# spdif_B.net
KiCad netlist of a schematic drawn in EAGLE
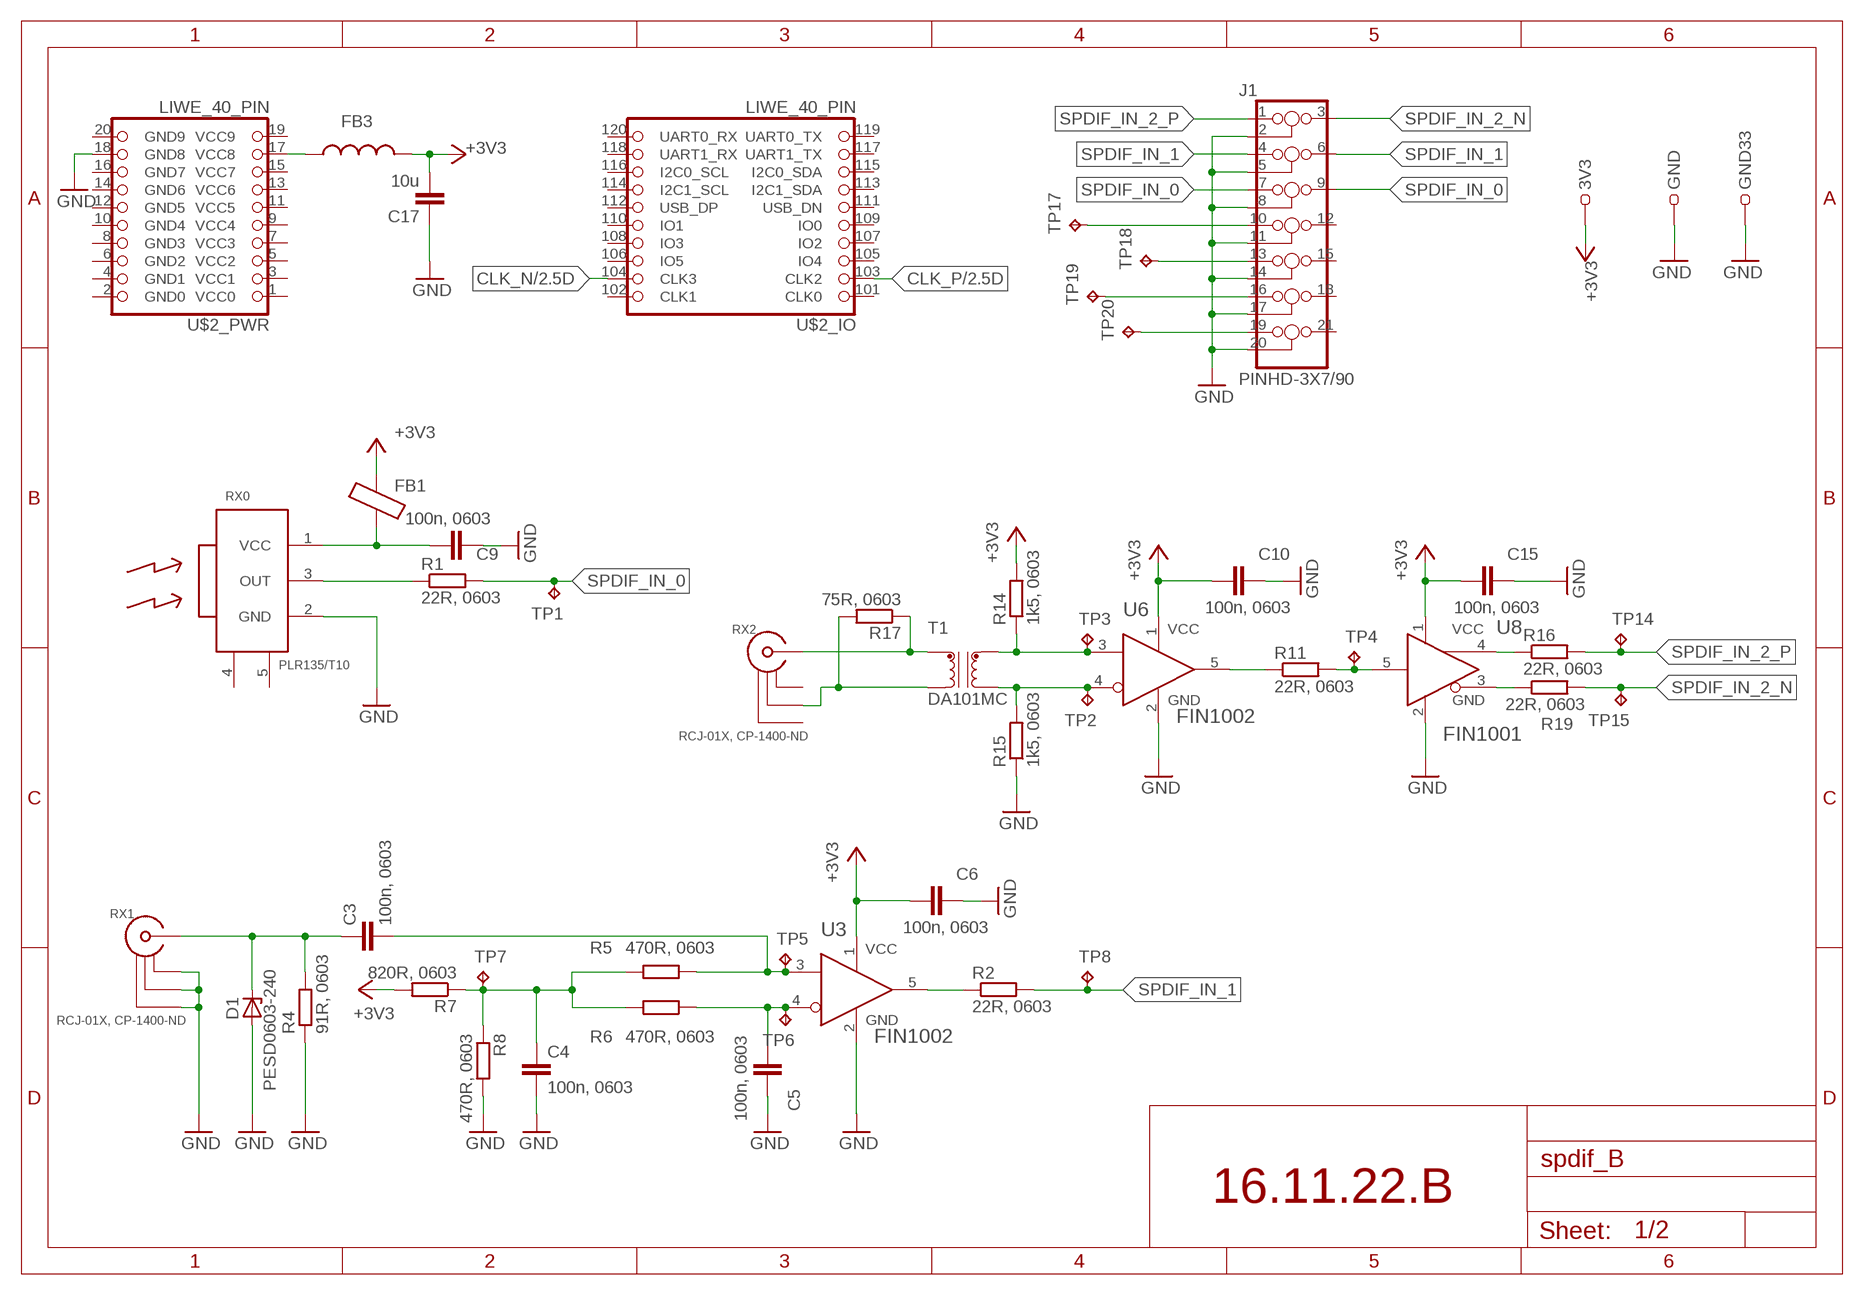
[diagram p0: schematic, sheet 1]
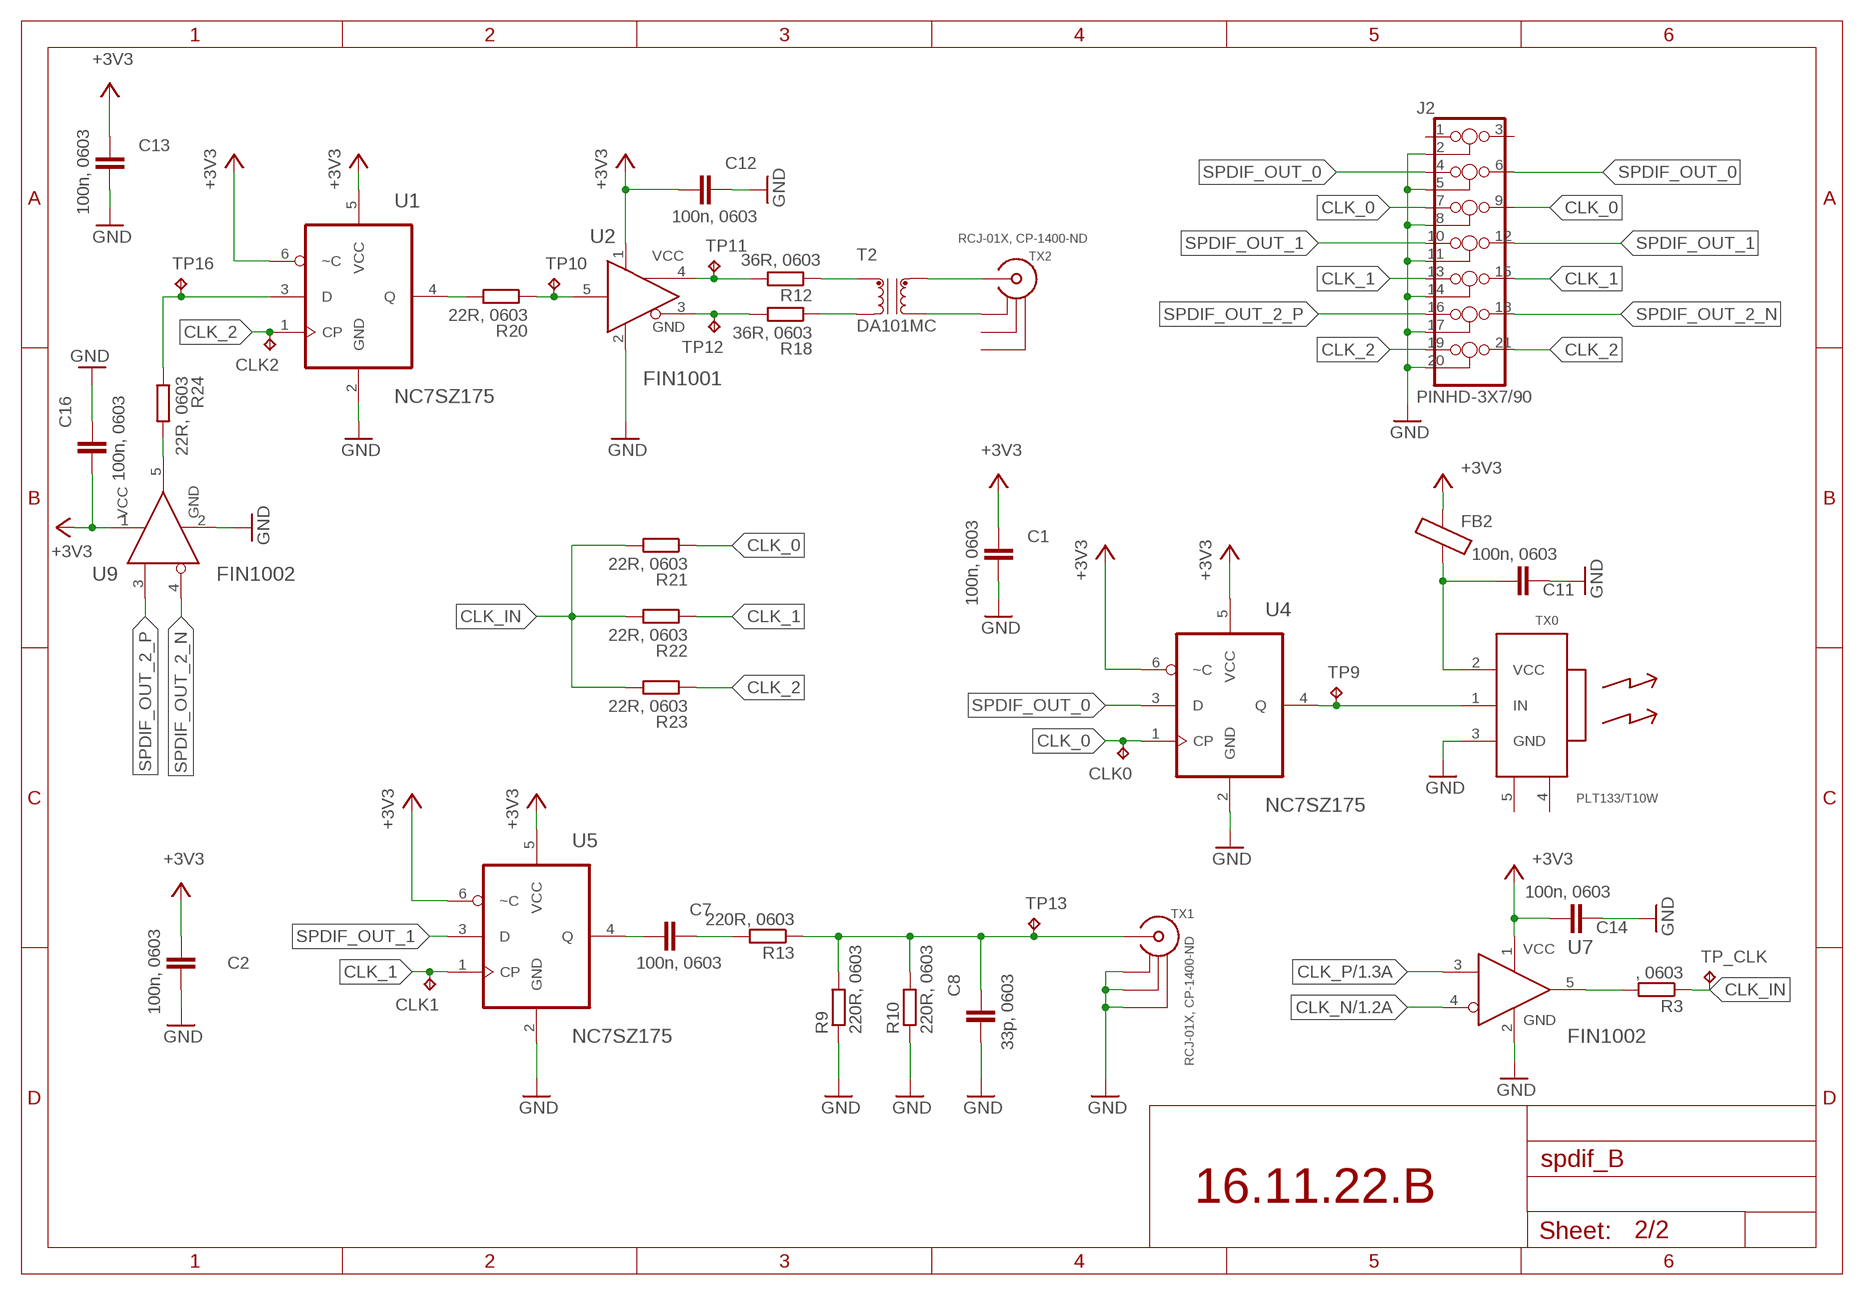
[diagram p1: schematic, sheet 2]

(export (version "E")
  (design (tool "Eeschema 10.0.6"))
  (components
    (comp (ref "3V3")
      (value "TEST-22-MULTICOMP")
      (footprint "eagle-import:TEST_1MM")
      (libsource (lib "eagle-import") (part "TEST-22-MULTICOMP"))
    )
    (comp (ref "C3")
      (value "100n, 0603")
      (footprint "eagle-import:C0603")
      (libsource (lib "eagle-import") (part "C-EUC0603"))
    )
    (comp (ref "C4")
      (value "100n, 0603")
      (footprint "eagle-import:C0603")
      (libsource (lib "eagle-import") (part "C-EUC0603"))
    )
    (comp (ref "C5")
      (value "100n, 0603")
      (footprint "eagle-import:C0603")
      (libsource (lib "eagle-import") (part "C-EUC0603"))
    )
    (comp (ref "C6")
      (value "100n, 0603")
      (footprint "eagle-import:C0603")
      (libsource (lib "eagle-import") (part "C-EUC0603"))
    )
    (comp (ref "C9")
      (value "100n, 0603")
      (footprint "eagle-import:C0603")
      (libsource (lib "eagle-import") (part "C-EUC0603"))
    )
    (comp (ref "C10")
      (value "100n, 0603")
      (footprint "eagle-import:C0603")
      (libsource (lib "eagle-import") (part "C-EUC0603"))
    )
    (comp (ref "C15")
      (value "100n, 0603")
      (footprint "eagle-import:C0603")
      (libsource (lib "eagle-import") (part "C-EUC0603"))
    )
    (comp (ref "C17")
      (value "10u")
      (footprint "eagle-import:C0805")
      (libsource (lib "eagle-import") (part "C-EUC0805"))
    )
    (comp (ref "D1")
      (value "PESD0603-240")
      (footprint "eagle-import:L0603")
      (libsource (lib "eagle-import") (part "ZDPESD0603-240"))
    )
    (comp (ref "FB1")
      (value "FB_0603")
      (footprint "eagle-import:L0603")
      (libsource (lib "eagle-import") (part "FB_0603"))
    )
    (comp (ref "FB3")
      (value "L0603(1608)")
      (footprint "eagle-import:L0603")
      (libsource (lib "eagle-import") (part "L0603(1608)"))
    )
    (comp (ref "GND")
      (value "TEST-22-MULTICOMP")
      (footprint "eagle-import:TEST_1MM")
      (libsource (lib "eagle-import") (part "TEST-22-MULTICOMP"))
    )
    (comp (ref "GND33")
      (value "TEST-22-MULTICOMP")
      (footprint "eagle-import:TEST_1MM")
      (libsource (lib "eagle-import") (part "TEST-22-MULTICOMP"))
    )
    (comp (ref "J1")
      (value "PINHD-3X7/90")
      (footprint "eagle-import:3X07_90")
      (libsource (lib "eagle-import") (part "PINHD-3X7/90"))
    )
    (comp (ref "R1")
      (value "22R, 0603")
      (footprint "eagle-import:R0603")
      (libsource (lib "eagle-import") (part "R-EU_R0603"))
    )
    (comp (ref "R2")
      (value "22R, 0603")
      (footprint "eagle-import:R0603")
      (libsource (lib "eagle-import") (part "R-EU_R0603"))
    )
    (comp (ref "R4")
      (value "91R, 0603")
      (footprint "eagle-import:R0603")
      (libsource (lib "eagle-import") (part "R-EU_R0603"))
    )
    (comp (ref "R5")
      (value "470R, 0603")
      (footprint "eagle-import:R0603")
      (libsource (lib "eagle-import") (part "R-EU_R0603"))
    )
    (comp (ref "R6")
      (value "470R, 0603")
      (footprint "eagle-import:R0603")
      (libsource (lib "eagle-import") (part "R-EU_R0603"))
    )
    (comp (ref "R7")
      (value "820R, 0603")
      (footprint "eagle-import:R0603")
      (libsource (lib "eagle-import") (part "R-EU_R0603"))
    )
    (comp (ref "R8")
      (value "470R, 0603")
      (footprint "eagle-import:R0603")
      (libsource (lib "eagle-import") (part "R-EU_R0603"))
    )
    (comp (ref "R11")
      (value "22R, 0603")
      (footprint "eagle-import:R0603")
      (libsource (lib "eagle-import") (part "R-EU_R0603"))
    )
    (comp (ref "R14")
      (value "1k5, 0603")
      (footprint "eagle-import:R0603")
      (libsource (lib "eagle-import") (part "R-EU_R0603"))
    )
    (comp (ref "R15")
      (value "1k5, 0603")
      (footprint "eagle-import:R0603")
      (libsource (lib "eagle-import") (part "R-EU_R0603"))
    )
    (comp (ref "R16")
      (value "22R, 0603")
      (footprint "eagle-import:R0603")
      (libsource (lib "eagle-import") (part "R-EU_R0603"))
    )
    (comp (ref "R17")
      (value "75R, 0603")
      (footprint "eagle-import:R0603")
      (libsource (lib "eagle-import") (part "R-EU_R0603"))
    )
    (comp (ref "R19")
      (value "22R, 0603")
      (footprint "eagle-import:R0603")
      (libsource (lib "eagle-import") (part "R-EU_R0603"))
    )
    (comp (ref "RX0")
      (value "PLR135/T10")
      (footprint "eagle-import:PLR135_T10")
      (libsource (lib "eagle-import") (part "PLR135_T10"))
    )
    (comp (ref "RX1")
      (value "RCJ-01X, CP-1400-ND")
      (footprint "eagle-import:RCJ-01X")
      (libsource (lib "eagle-import") (part "RCJ-01X"))
    )
    (comp (ref "RX2")
      (value "RCJ-01X, CP-1400-ND")
      (footprint "eagle-import:RCJ-01X")
      (libsource (lib "eagle-import") (part "RCJ-01X"))
    )
    (comp (ref "T1")
      (value "DA101MC")
      (footprint "eagle-import:DA101MC")
      (libsource (lib "eagle-import") (part "DA101MC"))
    )
    (comp (ref "TP1")
      (value "TPB1,27")
      (footprint "eagle-import:B1,27")
      (libsource (lib "eagle-import") (part "TPB1,27"))
    )
    (comp (ref "TP2")
      (value "TPB1,27")
      (footprint "eagle-import:B1,27")
      (libsource (lib "eagle-import") (part "TPB1,27"))
    )
    (comp (ref "TP3")
      (value "TPB1,27")
      (footprint "eagle-import:B1,27")
      (libsource (lib "eagle-import") (part "TPB1,27"))
    )
    (comp (ref "TP4")
      (value "TPB1,27")
      (footprint "eagle-import:B1,27")
      (libsource (lib "eagle-import") (part "TPB1,27"))
    )
    (comp (ref "TP5")
      (value "TPB1,27")
      (footprint "eagle-import:B1,27")
      (libsource (lib "eagle-import") (part "TPB1,27"))
    )
    (comp (ref "TP6")
      (value "TPB1,27")
      (footprint "eagle-import:B1,27")
      (libsource (lib "eagle-import") (part "TPB1,27"))
    )
    (comp (ref "TP7")
      (value "TPB1,27")
      (footprint "eagle-import:B1,27")
      (libsource (lib "eagle-import") (part "TPB1,27"))
    )
    (comp (ref "TP8")
      (value "TPB1,27")
      (footprint "eagle-import:B1,27")
      (libsource (lib "eagle-import") (part "TPB1,27"))
    )
    (comp (ref "TP14")
      (value "TPB1,27")
      (footprint "eagle-import:B1,27")
      (libsource (lib "eagle-import") (part "TPB1,27"))
    )
    (comp (ref "TP15")
      (value "TPB1,27")
      (footprint "eagle-import:B1,27")
      (libsource (lib "eagle-import") (part "TPB1,27"))
    )
    (comp (ref "TP17")
      (value "TPB1,27")
      (footprint "eagle-import:B1,27")
      (libsource (lib "eagle-import") (part "TPB1,27"))
    )
    (comp (ref "TP18")
      (value "TPB1,27")
      (footprint "eagle-import:B1,27")
      (libsource (lib "eagle-import") (part "TPB1,27"))
    )
    (comp (ref "TP19")
      (value "TPB1,27")
      (footprint "eagle-import:B1,27")
      (libsource (lib "eagle-import") (part "TPB1,27"))
    )
    (comp (ref "TP20")
      (value "TPB1,27")
      (footprint "eagle-import:B1,27")
      (libsource (lib "eagle-import") (part "TPB1,27"))
    )
    (comp (ref "U$2")
      (value "LIWE_40_PIN")
      (footprint "eagle-import:LIWE_40_PIN_8X8")
      (libsource (lib "eagle-import") (part "LIWE_40_PIN"))
    )
    (comp (ref "U3")
      (value "FIN1002")
      (footprint "eagle-import:SOT95P280X140-5N")
      (libsource (lib "eagle-import") (part "FIN1002"))
    )
    (comp (ref "U6")
      (value "FIN1002")
      (footprint "eagle-import:SOT95P280X140-5N")
      (libsource (lib "eagle-import") (part "FIN1002"))
    )
    (comp (ref "U8")
      (value "FIN1001")
      (footprint "eagle-import:SOT95P280X140-5N")
      (libsource (lib "eagle-import") (part "FIN1001"))
    )
    (comp (ref "C1")
      (value "100n, 0603")
      (footprint "eagle-import:C0603")
      (libsource (lib "eagle-import") (part "C-EUC0603"))
    )
    (comp (ref "C2")
      (value "100n, 0603")
      (footprint "eagle-import:C0603")
      (libsource (lib "eagle-import") (part "C-EUC0603"))
    )
    (comp (ref "C7")
      (value "100n, 0603")
      (footprint "eagle-import:C0603")
      (libsource (lib "eagle-import") (part "C-EUC0603"))
    )
    (comp (ref "C8")
      (value "33p, 0603")
      (footprint "eagle-import:C0603")
      (libsource (lib "eagle-import") (part "C-EUC0603"))
    )
    (comp (ref "C11")
      (value "100n, 0603")
      (footprint "eagle-import:C0603")
      (libsource (lib "eagle-import") (part "C-EUC0603"))
    )
    (comp (ref "C12")
      (value "100n, 0603")
      (footprint "eagle-import:C0603")
      (libsource (lib "eagle-import") (part "C-EUC0603"))
    )
    (comp (ref "C13")
      (value "100n, 0603")
      (footprint "eagle-import:C0603")
      (libsource (lib "eagle-import") (part "C-EUC0603"))
    )
    (comp (ref "C14")
      (value "100n, 0603")
      (footprint "eagle-import:C0603")
      (libsource (lib "eagle-import") (part "C-EUC0603"))
    )
    (comp (ref "C16")
      (value "100n, 0603")
      (footprint "eagle-import:C0603")
      (libsource (lib "eagle-import") (part "C-EUC0603"))
    )
    (comp (ref "CLK0")
      (value "TPB1,27")
      (footprint "eagle-import:B1,27")
      (libsource (lib "eagle-import") (part "TPB1,27"))
    )
    (comp (ref "CLK1")
      (value "TPB1,27")
      (footprint "eagle-import:B1,27")
      (libsource (lib "eagle-import") (part "TPB1,27"))
    )
    (comp (ref "CLK2")
      (value "TPB1,27")
      (footprint "eagle-import:B1,27")
      (libsource (lib "eagle-import") (part "TPB1,27"))
    )
    (comp (ref "FB2")
      (value "FB_0603")
      (footprint "eagle-import:L0603")
      (libsource (lib "eagle-import") (part "FB_0603"))
    )
    (comp (ref "J2")
      (value "PINHD-3X7/90")
      (footprint "eagle-import:3X07_90")
      (libsource (lib "eagle-import") (part "PINHD-3X7/90"))
    )
    (comp (ref "R3")
      (value ", 0603")
      (footprint "eagle-import:R0603")
      (libsource (lib "eagle-import") (part "R-EU_R0603"))
    )
    (comp (ref "R9")
      (value "220R, 0603")
      (footprint "eagle-import:R0603")
      (libsource (lib "eagle-import") (part "R-EU_R0603"))
    )
    (comp (ref "R10")
      (value "220R, 0603")
      (footprint "eagle-import:R0603")
      (libsource (lib "eagle-import") (part "R-EU_R0603"))
    )
    (comp (ref "R12")
      (value "36R, 0603")
      (footprint "eagle-import:R0603")
      (libsource (lib "eagle-import") (part "R-EU_R0603"))
    )
    (comp (ref "R13")
      (value "220R, 0603")
      (footprint "eagle-import:R0603")
      (libsource (lib "eagle-import") (part "R-EU_R0603"))
    )
    (comp (ref "R18")
      (value "36R, 0603")
      (footprint "eagle-import:R0603")
      (libsource (lib "eagle-import") (part "R-EU_R0603"))
    )
    (comp (ref "R20")
      (value "22R, 0603")
      (footprint "eagle-import:R0603")
      (libsource (lib "eagle-import") (part "R-EU_R0603"))
    )
    (comp (ref "R21")
      (value "22R, 0603")
      (footprint "eagle-import:R0603")
      (libsource (lib "eagle-import") (part "R-EU_R0603"))
    )
    (comp (ref "R22")
      (value "22R, 0603")
      (footprint "eagle-import:R0603")
      (libsource (lib "eagle-import") (part "R-EU_R0603"))
    )
    (comp (ref "R23")
      (value "22R, 0603")
      (footprint "eagle-import:R0603")
      (libsource (lib "eagle-import") (part "R-EU_R0603"))
    )
    (comp (ref "R24")
      (value "22R, 0603")
      (footprint "eagle-import:R0603")
      (libsource (lib "eagle-import") (part "R-EU_R0603"))
    )
    (comp (ref "T2")
      (value "DA101MC")
      (footprint "eagle-import:DA101MC")
      (libsource (lib "eagle-import") (part "DA101MC"))
    )
    (comp (ref "TP9")
      (value "TPB1,27")
      (footprint "eagle-import:B1,27")
      (libsource (lib "eagle-import") (part "TPB1,27"))
    )
    (comp (ref "TP10")
      (value "TPB1,27")
      (footprint "eagle-import:B1,27")
      (libsource (lib "eagle-import") (part "TPB1,27"))
    )
    (comp (ref "TP11")
      (value "TPB1,27")
      (footprint "eagle-import:B1,27")
      (libsource (lib "eagle-import") (part "TPB1,27"))
    )
    (comp (ref "TP12")
      (value "TPB1,27")
      (footprint "eagle-import:B1,27")
      (libsource (lib "eagle-import") (part "TPB1,27"))
    )
    (comp (ref "TP13")
      (value "TPB1,27")
      (footprint "eagle-import:B1,27")
      (libsource (lib "eagle-import") (part "TPB1,27"))
    )
    (comp (ref "TP16")
      (value "TPB1,27")
      (footprint "eagle-import:B1,27")
      (libsource (lib "eagle-import") (part "TPB1,27"))
    )
    (comp (ref "TP_CLK")
      (value "TPB1,27")
      (footprint "eagle-import:B1,27")
      (libsource (lib "eagle-import") (part "TPB1,27"))
    )
    (comp (ref "TX0")
      (value "PLT133/T10W")
      (footprint "eagle-import:PLT133_T10W")
      (libsource (lib "eagle-import") (part "PLT133_T10W"))
    )
    (comp (ref "TX1")
      (value "RCJ-01X, CP-1400-ND")
      (footprint "eagle-import:RCJ-01X")
      (libsource (lib "eagle-import") (part "RCJ-01X"))
    )
    (comp (ref "TX2")
      (value "RCJ-01X, CP-1400-ND")
      (footprint "eagle-import:RCJ-01X")
      (libsource (lib "eagle-import") (part "RCJ-01X"))
    )
    (comp (ref "U1")
      (value "NC7SZ175")
      (footprint "eagle-import:SOT65P210X110-6N")
      (libsource (lib "eagle-import") (part "NC7SZ175"))
    )
    (comp (ref "U2")
      (value "FIN1001")
      (footprint "eagle-import:SOT95P280X140-5N")
      (libsource (lib "eagle-import") (part "FIN1001"))
    )
    (comp (ref "U4")
      (value "NC7SZ175")
      (footprint "eagle-import:SOT65P210X110-6N")
      (libsource (lib "eagle-import") (part "NC7SZ175"))
    )
    (comp (ref "U5")
      (value "NC7SZ175")
      (footprint "eagle-import:SOT65P210X110-6N")
      (libsource (lib "eagle-import") (part "NC7SZ175"))
    )
    (comp (ref "U7")
      (value "FIN1002")
      (footprint "eagle-import:SOT95P280X140-5N")
      (libsource (lib "eagle-import") (part "FIN1002"))
    )
    (comp (ref "U9")
      (value "FIN1002")
      (footprint "eagle-import:SOT95P280X140-5N")
      (libsource (lib "eagle-import") (part "FIN1002"))
    )
  )
  (nets
    (net (code "1") (name "+3V3") (class "Default")
      (node (ref "3V3") (pin "1") (pinfunction "1_1") (pintype "passive"))
      (node (ref "C1") (pin "2") (pinfunction "2_2") (pintype "passive"))
      (node (ref "C10") (pin "2") (pinfunction "2_2") (pintype "passive"))
      (node (ref "C12") (pin "2") (pinfunction "2_2") (pintype "passive"))
      (node (ref "C13") (pin "2") (pinfunction "2_2") (pintype "passive"))
      (node (ref "C14") (pin "2") (pinfunction "2_2") (pintype "passive"))
      (node (ref "C15") (pin "2") (pinfunction "2_2") (pintype "passive"))
      (node (ref "C16") (pin "2") (pinfunction "2_2") (pintype "passive"))
      (node (ref "C17") (pin "2") (pinfunction "2_2") (pintype "passive"))
      (node (ref "C2") (pin "2") (pinfunction "2_2") (pintype "passive"))
      (node (ref "C6") (pin "2") (pinfunction "2_2") (pintype "passive"))
      (node (ref "FB1") (pin "2") (pinfunction "P$2_2") (pintype "bidirectional"))
      (node (ref "FB2") (pin "2") (pinfunction "P$2_2") (pintype "bidirectional"))
      (node (ref "FB3") (pin "2") (pinfunction "2_2") (pintype "passive"))
      (node (ref "R14") (pin "2") (pinfunction "2_2") (pintype "passive"))
      (node (ref "R7") (pin "2") (pinfunction "2_2") (pintype "passive"))
      (node (ref "U1") (pin "5") (pinfunction "VCC_5") (pintype "power_in"))
      (node (ref "U1") (pin "6") (pinfunction "~{C}_6") (pintype "input"))
      (node (ref "U2") (pin "1") (pinfunction "VCC_1") (pintype "power_in"))
      (node (ref "U3") (pin "1") (pinfunction "VCC_1") (pintype "power_in"))
      (node (ref "U4") (pin "5") (pinfunction "VCC_5") (pintype "power_in"))
      (node (ref "U4") (pin "6") (pinfunction "~{C}_6") (pintype "input"))
      (node (ref "U5") (pin "5") (pinfunction "VCC_5") (pintype "power_in"))
      (node (ref "U5") (pin "6") (pinfunction "~{C}_6") (pintype "input"))
      (node (ref "U6") (pin "1") (pinfunction "VCC_1") (pintype "power_in"))
      (node (ref "U7") (pin "1") (pinfunction "VCC_1") (pintype "power_in"))
      (node (ref "U8") (pin "1") (pinfunction "VCC_1") (pintype "power_in"))
      (node (ref "U9") (pin "1") (pinfunction "VCC_1") (pintype "power_in"))
    )
    (net (code "2") (name "CLK_0") (class "Default")
      (node (ref "CLK0") (pin "TP") (pinfunction "TP_TP") (pintype "input"))
      (node (ref "J2") (pin "7") (pinfunction "7_7") (pintype "passive"))
      (node (ref "J2") (pin "9") (pinfunction "9_9") (pintype "passive"))
      (node (ref "R21") (pin "1") (pinfunction "1_1") (pintype "passive"))
      (node (ref "U4") (pin "1") (pinfunction "CP_1") (pintype "input"))
    )
    (net (code "3") (name "CLK_1") (class "Default")
      (node (ref "CLK1") (pin "TP") (pinfunction "TP_TP") (pintype "input"))
      (node (ref "J2") (pin "13") (pinfunction "13_13") (pintype "passive"))
      (node (ref "J2") (pin "15") (pinfunction "15_15") (pintype "passive"))
      (node (ref "R22") (pin "1") (pinfunction "1_1") (pintype "passive"))
      (node (ref "U5") (pin "1") (pinfunction "CP_1") (pintype "input"))
    )
    (net (code "4") (name "CLK_2") (class "Default")
      (node (ref "CLK2") (pin "TP") (pinfunction "TP_TP") (pintype "input"))
      (node (ref "J2") (pin "19") (pinfunction "19_19") (pintype "passive"))
      (node (ref "J2") (pin "21") (pinfunction "21_21") (pintype "passive"))
      (node (ref "R23") (pin "1") (pinfunction "1_1") (pintype "passive"))
      (node (ref "U1") (pin "1") (pinfunction "CP_1") (pintype "input"))
    )
    (net (code "5") (name "CLK_IN") (class "Default")
      (node (ref "R21") (pin "2") (pinfunction "2_2") (pintype "passive"))
      (node (ref "R22") (pin "2") (pinfunction "2_2") (pintype "passive"))
      (node (ref "R23") (pin "2") (pinfunction "2_2") (pintype "passive"))
      (node (ref "R3") (pin "1") (pinfunction "1_1") (pintype "passive"))
      (node (ref "TP_CLK") (pin "TP") (pinfunction "TP_TP") (pintype "input"))
    )
    (net (code "6") (name "CLK_N") (class "Default")
      (node (ref "U$2") (pin "104") (pinfunction "CLK3_104") (pintype "passive"))
      (node (ref "U7") (pin "4") (pinfunction "RIN-_4") (pintype "input"))
    )
    (net (code "7") (name "CLK_P") (class "Default")
      (node (ref "U$2") (pin "103") (pinfunction "CLK2_103") (pintype "passive"))
      (node (ref "U7") (pin "3") (pinfunction "RIN+_3") (pintype "input"))
    )
    (net (code "8") (name "GND") (class "Default")
      (node (ref "C1") (pin "1") (pinfunction "1_1") (pintype "passive"))
      (node (ref "C10") (pin "1") (pinfunction "1_1") (pintype "passive"))
      (node (ref "C11") (pin "1") (pinfunction "1_1") (pintype "passive"))
      (node (ref "C12") (pin "1") (pinfunction "1_1") (pintype "passive"))
      (node (ref "C13") (pin "1") (pinfunction "1_1") (pintype "passive"))
      (node (ref "C14") (pin "1") (pinfunction "1_1") (pintype "passive"))
      (node (ref "C15") (pin "1") (pinfunction "1_1") (pintype "passive"))
      (node (ref "C16") (pin "1") (pinfunction "1_1") (pintype "passive"))
      (node (ref "C17") (pin "1") (pinfunction "1_1") (pintype "passive"))
      (node (ref "C2") (pin "1") (pinfunction "1_1") (pintype "passive"))
      (node (ref "C4") (pin "2") (pinfunction "2_2") (pintype "passive"))
      (node (ref "C5") (pin "1") (pinfunction "1_1") (pintype "passive"))
      (node (ref "C6") (pin "1") (pinfunction "1_1") (pintype "passive"))
      (node (ref "C8") (pin "2") (pinfunction "2_2") (pintype "passive"))
      (node (ref "C9") (pin "1") (pinfunction "1_1") (pintype "passive"))
      (node (ref "D1") (pin "1") (pinfunction "A_1") (pintype "passive"))
      (node (ref "GND") (pin "1") (pinfunction "1_1") (pintype "passive"))
      (node (ref "GND33") (pin "1") (pinfunction "1_1") (pintype "passive"))
      (node (ref "J1") (pin "11") (pinfunction "11_11") (pintype "passive"))
      (node (ref "J1") (pin "14") (pinfunction "14_14") (pintype "passive"))
      (node (ref "J1") (pin "17") (pinfunction "17_17") (pintype "passive"))
      (node (ref "J1") (pin "2") (pinfunction "2_2") (pintype "passive"))
      (node (ref "J1") (pin "20") (pinfunction "20_20") (pintype "passive"))
      (node (ref "J1") (pin "5") (pinfunction "5_5") (pintype "passive"))
      (node (ref "J1") (pin "8") (pinfunction "8_8") (pintype "passive"))
      (node (ref "J2") (pin "11") (pinfunction "11_11") (pintype "passive"))
      (node (ref "J2") (pin "14") (pinfunction "14_14") (pintype "passive"))
      (node (ref "J2") (pin "17") (pinfunction "17_17") (pintype "passive"))
      (node (ref "J2") (pin "2") (pinfunction "2_2") (pintype "passive"))
      (node (ref "J2") (pin "20") (pinfunction "20_20") (pintype "passive"))
      (node (ref "J2") (pin "5") (pinfunction "5_5") (pintype "passive"))
      (node (ref "J2") (pin "8") (pinfunction "8_8") (pintype "passive"))
      (node (ref "R10") (pin "1") (pinfunction "1_1") (pintype "passive"))
      (node (ref "R15") (pin "1") (pinfunction "1_1") (pintype "passive"))
      (node (ref "R4") (pin "1") (pinfunction "1_1") (pintype "passive"))
      (node (ref "R8") (pin "2") (pinfunction "2_2") (pintype "passive"))
      (node (ref "R9") (pin "1") (pinfunction "1_1") (pintype "passive"))
      (node (ref "RX0") (pin "2") (pinfunction "GND_2") (pintype "output"))
      (node (ref "RX1") (pin "20") (pinfunction "GND1_20") (pintype "output"))
      (node (ref "RX1") (pin "21") (pinfunction "GND2_21") (pintype "output"))
      (node (ref "RX1") (pin "22") (pinfunction "GND3_22") (pintype "output"))
      (node (ref "TX0") (pin "3") (pinfunction "GND_3") (pintype "output"))
      (node (ref "TX1") (pin "20") (pinfunction "GND1_20") (pintype "output"))
      (node (ref "TX1") (pin "21") (pinfunction "GND2_21") (pintype "output"))
      (node (ref "TX1") (pin "22") (pinfunction "GND3_22") (pintype "output"))
      (node (ref "U$2") (pin "18") (pinfunction "GND8_18") (pintype "passive"))
      (node (ref "U1") (pin "2") (pinfunction "GND_2") (pintype "passive"))
      (node (ref "U2") (pin "2") (pinfunction "GND_2") (pintype "passive"))
      (node (ref "U3") (pin "2") (pinfunction "GND_2") (pintype "passive"))
      (node (ref "U4") (pin "2") (pinfunction "GND_2") (pintype "passive"))
      (node (ref "U5") (pin "2") (pinfunction "GND_2") (pintype "passive"))
      (node (ref "U6") (pin "2") (pinfunction "GND_2") (pintype "passive"))
      (node (ref "U7") (pin "2") (pinfunction "GND_2") (pintype "passive"))
      (node (ref "U8") (pin "2") (pinfunction "GND_2") (pintype "passive"))
      (node (ref "U9") (pin "2") (pinfunction "GND_2") (pintype "passive"))
    )
    (net (code "9") (name "Net-(C4-Pad1)") (class "Default")
      (node (ref "C4") (pin "1") (pinfunction "1_1") (pintype "passive"))
      (node (ref "R5") (pin "2") (pinfunction "2_2") (pintype "passive"))
      (node (ref "R6") (pin "2") (pinfunction "2_2") (pintype "passive"))
      (node (ref "R7") (pin "1") (pinfunction "1_1") (pintype "passive"))
      (node (ref "R8") (pin "1") (pinfunction "1_1") (pintype "passive"))
      (node (ref "TP7") (pin "TP") (pinfunction "TP_TP") (pintype "input"))
    )
    (net (code "10") (name "Net-(C7-Pad1)") (class "Default")
      (node (ref "C7") (pin "1") (pinfunction "1_1") (pintype "passive"))
      (node (ref "R13") (pin "2") (pinfunction "2_2") (pintype "passive"))
    )
    (net (code "11") (name "Net-(D1-C)") (class "Default")
      (node (ref "C3") (pin "1") (pinfunction "1_1") (pintype "passive"))
      (node (ref "D1") (pin "2") (pinfunction "C_2") (pintype "passive"))
      (node (ref "R4") (pin "2") (pinfunction "2_2") (pintype "passive"))
      (node (ref "RX1") (pin "1") (pinfunction "SIG_1") (pintype "output"))
    )
    (net (code "12") (name "Net-(FB1-P$1)") (class "Default")
      (node (ref "C9") (pin "2") (pinfunction "2_2") (pintype "passive"))
      (node (ref "FB1") (pin "1") (pinfunction "P$1_1") (pintype "bidirectional"))
      (node (ref "RX0") (pin "1") (pinfunction "VCC_1") (pintype "output"))
    )
    (net (code "13") (name "Net-(FB2-P$1)") (class "Default")
      (node (ref "C11") (pin "2") (pinfunction "2_2") (pintype "passive"))
      (node (ref "FB2") (pin "1") (pinfunction "P$1_1") (pintype "bidirectional"))
      (node (ref "TX0") (pin "2") (pinfunction "VCC_2") (pintype "output"))
    )
    (net (code "14") (name "Net-(J1-Pad10)") (class "Default")
      (node (ref "J1") (pin "10") (pinfunction "10_10") (pintype "passive"))
      (node (ref "TP17") (pin "TP") (pinfunction "TP_TP") (pintype "input"))
    )
    (net (code "15") (name "Net-(J1-Pad13)") (class "Default")
      (node (ref "J1") (pin "13") (pinfunction "13_13") (pintype "passive"))
      (node (ref "TP18") (pin "TP") (pinfunction "TP_TP") (pintype "input"))
    )
    (net (code "16") (name "Net-(J1-Pad16)") (class "Default")
      (node (ref "J1") (pin "16") (pinfunction "16_16") (pintype "passive"))
      (node (ref "TP19") (pin "TP") (pinfunction "TP_TP") (pintype "input"))
    )
    (net (code "17") (name "Net-(J1-Pad19)") (class "Default")
      (node (ref "J1") (pin "19") (pinfunction "19_19") (pintype "passive"))
      (node (ref "TP20") (pin "TP") (pinfunction "TP_TP") (pintype "input"))
    )
    (net (code "18") (name "Net-(R12-Pad1)") (class "Default")
      (node (ref "R12") (pin "1") (pinfunction "1_1") (pintype "passive"))
      (node (ref "T2") (pin "1") (pinfunction "1_1") (pintype "bidirectional"))
    )
    (net (code "19") (name "Net-(R18-Pad1)") (class "Default")
      (node (ref "R18") (pin "1") (pinfunction "1_1") (pintype "passive"))
      (node (ref "T2") (pin "3") (pinfunction "3_3") (pintype "bidirectional"))
    )
    (net (code "20") (name "Net-(RX0-OUT)") (class "Default")
      (node (ref "R1") (pin "1") (pinfunction "1_1") (pintype "passive"))
      (node (ref "RX0") (pin "3") (pinfunction "OUT_3") (pintype "output"))
    )
    (net (code "21") (name "Net-(RX2-GND2)") (class "Default")
      (node (ref "R17") (pin "2") (pinfunction "2_2") (pintype "passive"))
      (node (ref "RX2") (pin "21") (pinfunction "GND2_21") (pintype "output"))
      (node (ref "T1") (pin "3") (pinfunction "3_3") (pintype "bidirectional"))
    )
    (net (code "22") (name "Net-(RX2-SIG)") (class "Default")
      (node (ref "R17") (pin "1") (pinfunction "1_1") (pintype "passive"))
      (node (ref "RX2") (pin "1") (pinfunction "SIG_1") (pintype "output"))
      (node (ref "T1") (pin "1") (pinfunction "1_1") (pintype "bidirectional"))
    )
    (net (code "23") (name "Net-(TX0-IN)") (class "Default")
      (node (ref "TP9") (pin "TP") (pinfunction "TP_TP") (pintype "input"))
      (node (ref "TX0") (pin "1") (pinfunction "IN_1") (pintype "output"))
      (node (ref "U4") (pin "4") (pinfunction "Q_4") (pintype "output"))
    )
    (net (code "24") (name "Net-(TX1-SIG)") (class "Default")
      (node (ref "C8") (pin "1") (pinfunction "1_1") (pintype "passive"))
      (node (ref "R10") (pin "2") (pinfunction "2_2") (pintype "passive"))
      (node (ref "R13") (pin "1") (pinfunction "1_1") (pintype "passive"))
      (node (ref "R9") (pin "2") (pinfunction "2_2") (pintype "passive"))
      (node (ref "TP13") (pin "TP") (pinfunction "TP_TP") (pintype "input"))
      (node (ref "TX1") (pin "1") (pinfunction "SIG_1") (pintype "output"))
    )
    (net (code "25") (name "Net-(TX2-GND1)") (class "Default")
      (node (ref "T2") (pin "4") (pinfunction "4_4") (pintype "bidirectional"))
      (node (ref "TX2") (pin "20") (pinfunction "GND1_20") (pintype "output"))
    )
    (net (code "26") (name "Net-(TX2-SIG)") (class "Default")
      (node (ref "T2") (pin "6") (pinfunction "6_6") (pintype "bidirectional"))
      (node (ref "TX2") (pin "1") (pinfunction "SIG_1") (pintype "output"))
    )
    (net (code "27") (name "Net-(U$2B-VCC8)") (class "Default")
      (node (ref "FB3") (pin "1") (pinfunction "1_1") (pintype "passive"))
      (node (ref "U$2") (pin "17") (pinfunction "VCC8_17") (pintype "passive"))
    )
    (net (code "28") (name "Net-(U1-D)") (class "Default")
      (node (ref "R24") (pin "1") (pinfunction "1_1") (pintype "passive"))
      (node (ref "TP16") (pin "TP") (pinfunction "TP_TP") (pintype "input"))
      (node (ref "U1") (pin "3") (pinfunction "D_3") (pintype "input"))
    )
    (net (code "29") (name "Net-(U1-Q)") (class "Default")
      (node (ref "R20") (pin "2") (pinfunction "2_2") (pintype "passive"))
      (node (ref "U1") (pin "4") (pinfunction "Q_4") (pintype "output"))
    )
    (net (code "30") (name "Net-(U2-RIN)") (class "Default")
      (node (ref "R20") (pin "1") (pinfunction "1_1") (pintype "passive"))
      (node (ref "TP10") (pin "TP") (pinfunction "TP_TP") (pintype "input"))
      (node (ref "U2") (pin "5") (pinfunction "RIN_5") (pintype "input"))
    )
    (net (code "31") (name "Net-(U2-ROUT+)") (class "Default")
      (node (ref "R12") (pin "2") (pinfunction "2_2") (pintype "passive"))
      (node (ref "TP11") (pin "TP") (pinfunction "TP_TP") (pintype "input"))
      (node (ref "U2") (pin "4") (pinfunction "ROUT+_4") (pintype "output"))
    )
    (net (code "32") (name "Net-(U2-ROUT-)") (class "Default")
      (node (ref "R18") (pin "2") (pinfunction "2_2") (pintype "passive"))
      (node (ref "TP12") (pin "TP") (pinfunction "TP_TP") (pintype "input"))
      (node (ref "U2") (pin "3") (pinfunction "ROUT-_3") (pintype "output"))
    )
    (net (code "33") (name "Net-(U3-RIN+)") (class "Default")
      (node (ref "C3") (pin "2") (pinfunction "2_2") (pintype "passive"))
      (node (ref "R5") (pin "1") (pinfunction "1_1") (pintype "passive"))
      (node (ref "TP5") (pin "TP") (pinfunction "TP_TP") (pintype "input"))
      (node (ref "U3") (pin "3") (pinfunction "RIN+_3") (pintype "input"))
    )
    (net (code "34") (name "Net-(U3-RIN-)") (class "Default")
      (node (ref "C5") (pin "2") (pinfunction "2_2") (pintype "passive"))
      (node (ref "R6") (pin "1") (pinfunction "1_1") (pintype "passive"))
      (node (ref "TP6") (pin "TP") (pinfunction "TP_TP") (pintype "input"))
      (node (ref "U3") (pin "4") (pinfunction "RIN-_4") (pintype "input"))
    )
    (net (code "35") (name "Net-(U3-ROUT)") (class "Default")
      (node (ref "R2") (pin "1") (pinfunction "1_1") (pintype "passive"))
      (node (ref "U3") (pin "5") (pinfunction "ROUT_5") (pintype "output"))
    )
    (net (code "36") (name "Net-(U5-Q)") (class "Default")
      (node (ref "C7") (pin "2") (pinfunction "2_2") (pintype "passive"))
      (node (ref "U5") (pin "4") (pinfunction "Q_4") (pintype "output"))
    )
    (net (code "37") (name "Net-(U6-RIN+)") (class "Default")
      (node (ref "R14") (pin "1") (pinfunction "1_1") (pintype "passive"))
      (node (ref "T1") (pin "6") (pinfunction "6_6") (pintype "bidirectional"))
      (node (ref "TP3") (pin "TP") (pinfunction "TP_TP") (pintype "input"))
      (node (ref "U6") (pin "3") (pinfunction "RIN+_3") (pintype "input"))
    )
    (net (code "38") (name "Net-(U6-RIN-)") (class "Default")
      (node (ref "R15") (pin "2") (pinfunction "2_2") (pintype "passive"))
      (node (ref "T1") (pin "4") (pinfunction "4_4") (pintype "bidirectional"))
      (node (ref "TP2") (pin "TP") (pinfunction "TP_TP") (pintype "input"))
      (node (ref "U6") (pin "4") (pinfunction "RIN-_4") (pintype "input"))
    )
    (net (code "39") (name "Net-(U6-ROUT)") (class "Default")
      (node (ref "R11") (pin "1") (pinfunction "1_1") (pintype "passive"))
      (node (ref "U6") (pin "5") (pinfunction "ROUT_5") (pintype "output"))
    )
    (net (code "40") (name "Net-(U7-ROUT)") (class "Default")
      (node (ref "R3") (pin "2") (pinfunction "2_2") (pintype "passive"))
      (node (ref "U7") (pin "5") (pinfunction "ROUT_5") (pintype "output"))
    )
    (net (code "41") (name "Net-(U8-RIN)") (class "Default")
      (node (ref "R11") (pin "2") (pinfunction "2_2") (pintype "passive"))
      (node (ref "TP4") (pin "TP") (pinfunction "TP_TP") (pintype "input"))
      (node (ref "U8") (pin "5") (pinfunction "RIN_5") (pintype "input"))
    )
    (net (code "42") (name "Net-(U8-ROUT+)") (class "Default")
      (node (ref "R16") (pin "1") (pinfunction "1_1") (pintype "passive"))
      (node (ref "U8") (pin "4") (pinfunction "ROUT+_4") (pintype "output"))
    )
    (net (code "43") (name "Net-(U8-ROUT-)") (class "Default")
      (node (ref "R19") (pin "1") (pinfunction "1_1") (pintype "passive"))
      (node (ref "U8") (pin "3") (pinfunction "ROUT-_3") (pintype "output"))
    )
    (net (code "44") (name "Net-(U9-ROUT)") (class "Default")
      (node (ref "R24") (pin "2") (pinfunction "2_2") (pintype "passive"))
      (node (ref "U9") (pin "5") (pinfunction "ROUT_5") (pintype "output"))
    )
    (net (code "45") (name "SPDIF_IN_0") (class "Default")
      (node (ref "J1") (pin "7") (pinfunction "7_7") (pintype "passive"))
      (node (ref "J1") (pin "9") (pinfunction "9_9") (pintype "passive"))
      (node (ref "R1") (pin "2") (pinfunction "2_2") (pintype "passive"))
      (node (ref "TP1") (pin "TP") (pinfunction "TP_TP") (pintype "input"))
    )
    (net (code "46") (name "SPDIF_IN_1") (class "Default")
      (node (ref "J1") (pin "4") (pinfunction "4_4") (pintype "passive"))
      (node (ref "J1") (pin "6") (pinfunction "6_6") (pintype "passive"))
      (node (ref "R2") (pin "2") (pinfunction "2_2") (pintype "passive"))
      (node (ref "TP8") (pin "TP") (pinfunction "TP_TP") (pintype "input"))
    )
    (net (code "47") (name "SPDIF_IN_2_N") (class "Default")
      (node (ref "J1") (pin "3") (pinfunction "3_3") (pintype "passive"))
      (node (ref "R19") (pin "2") (pinfunction "2_2") (pintype "passive"))
      (node (ref "TP15") (pin "TP") (pinfunction "TP_TP") (pintype "input"))
    )
    (net (code "48") (name "SPDIF_IN_2_P") (class "Default")
      (node (ref "J1") (pin "1") (pinfunction "1_1") (pintype "passive"))
      (node (ref "R16") (pin "2") (pinfunction "2_2") (pintype "passive"))
      (node (ref "TP14") (pin "TP") (pinfunction "TP_TP") (pintype "input"))
    )
    (net (code "49") (name "SPDIF_OUT_0") (class "Default")
      (node (ref "J2") (pin "4") (pinfunction "4_4") (pintype "passive"))
      (node (ref "J2") (pin "6") (pinfunction "6_6") (pintype "passive"))
      (node (ref "U4") (pin "3") (pinfunction "D_3") (pintype "input"))
    )
    (net (code "50") (name "SPDIF_OUT_1") (class "Default")
      (node (ref "J2") (pin "10") (pinfunction "10_10") (pintype "passive"))
      (node (ref "J2") (pin "12") (pinfunction "12_12") (pintype "passive"))
      (node (ref "U5") (pin "3") (pinfunction "D_3") (pintype "input"))
    )
    (net (code "51") (name "SPDIF_OUT_2_N") (class "Default")
      (node (ref "J2") (pin "18") (pinfunction "18_18") (pintype "passive"))
      (node (ref "U9") (pin "4") (pinfunction "RIN-_4") (pintype "input"))
    )
    (net (code "52") (name "SPDIF_OUT_2_P") (class "Default")
      (node (ref "J2") (pin "16") (pinfunction "16_16") (pintype "passive"))
      (node (ref "U9") (pin "3") (pinfunction "RIN+_3") (pintype "input"))
    )
    (net (code "53") (name "unconnected-(J1-Pad12)") (class "Default")
      (node (ref "J1") (pin "12") (pinfunction "12_12") (pintype "passive"))
    )
    (net (code "54") (name "unconnected-(J1-Pad15)") (class "Default")
      (node (ref "J1") (pin "15") (pinfunction "15_15") (pintype "passive"))
    )
    (net (code "55") (name "unconnected-(J1-Pad18)") (class "Default")
      (node (ref "J1") (pin "18") (pinfunction "18_18") (pintype "passive"))
    )
    (net (code "56") (name "unconnected-(J1-Pad21)") (class "Default")
      (node (ref "J1") (pin "21") (pinfunction "21_21") (pintype "passive"))
    )
    (net (code "57") (name "unconnected-(J2-Pad1)") (class "Default")
      (node (ref "J2") (pin "1") (pinfunction "1_1") (pintype "passive"))
    )
    (net (code "58") (name "unconnected-(J2-Pad3)") (class "Default")
      (node (ref "J2") (pin "3") (pinfunction "3_3") (pintype "passive"))
    )
    (net (code "59") (name "unconnected-(RX0-NC0-Pad4)") (class "Default")
      (node (ref "RX0") (pin "4") (pinfunction "NC0_4") (pintype "output"))
    )
    (net (code "60") (name "unconnected-(RX0-NC1-Pad5)") (class "Default")
      (node (ref "RX0") (pin "5") (pinfunction "NC1_5") (pintype "output"))
    )
    (net (code "61") (name "unconnected-(RX2-GND1-Pad20)") (class "Default")
      (node (ref "RX2") (pin "20") (pinfunction "GND1_20") (pintype "output"))
    )
    (net (code "62") (name "unconnected-(RX2-GND3-Pad22)") (class "Default")
      (node (ref "RX2") (pin "22") (pinfunction "GND3_22") (pintype "output"))
    )
    (net (code "63") (name "unconnected-(TX0-NC0-Pad4)") (class "Default")
      (node (ref "TX0") (pin "4") (pinfunction "NC0_4") (pintype "output"))
    )
    (net (code "64") (name "unconnected-(TX0-NC1-Pad5)") (class "Default")
      (node (ref "TX0") (pin "5") (pinfunction "NC1_5") (pintype "output"))
    )
    (net (code "65") (name "unconnected-(TX2-GND2-Pad21)") (class "Default")
      (node (ref "TX2") (pin "21") (pinfunction "GND2_21") (pintype "output"))
    )
    (net (code "66") (name "unconnected-(TX2-GND3-Pad22)") (class "Default")
      (node (ref "TX2") (pin "22") (pinfunction "GND3_22") (pintype "output"))
    )
    (net (code "67") (name "unconnected-(U$2A-CLK0-Pad101)") (class "Default")
      (node (ref "U$2") (pin "101") (pinfunction "CLK0_101") (pintype "passive"))
    )
    (net (code "68") (name "unconnected-(U$2A-CLK1-Pad102)") (class "Default")
      (node (ref "U$2") (pin "102") (pinfunction "CLK1_102") (pintype "passive"))
    )
    (net (code "69") (name "unconnected-(U$2A-I2C0_SCL-Pad116)") (class "Default")
      (node (ref "U$2") (pin "116") (pinfunction "I2C0_SCL_116") (pintype "passive"))
    )
    (net (code "70") (name "unconnected-(U$2A-I2C0_SDA-Pad115)") (class "Default")
      (node (ref "U$2") (pin "115") (pinfunction "I2C0_SDA_115") (pintype "passive"))
    )
    (net (code "71") (name "unconnected-(U$2A-I2C1_SCL-Pad114)") (class "Default")
      (node (ref "U$2") (pin "114") (pinfunction "I2C1_SCL_114") (pintype "passive"))
    )
    (net (code "72") (name "unconnected-(U$2A-I2C1_SDA-Pad113)") (class "Default")
      (node (ref "U$2") (pin "113") (pinfunction "I2C1_SDA_113") (pintype "passive"))
    )
    (net (code "73") (name "unconnected-(U$2A-IO0-Pad109)") (class "Default")
      (node (ref "U$2") (pin "109") (pinfunction "IO0_109") (pintype "passive"))
    )
    (net (code "74") (name "unconnected-(U$2A-IO1-Pad110)") (class "Default")
      (node (ref "U$2") (pin "110") (pinfunction "IO1_110") (pintype "passive"))
    )
    (net (code "75") (name "unconnected-(U$2A-IO2-Pad107)") (class "Default")
      (node (ref "U$2") (pin "107") (pinfunction "IO2_107") (pintype "passive"))
    )
    (net (code "76") (name "unconnected-(U$2A-IO3-Pad108)") (class "Default")
      (node (ref "U$2") (pin "108") (pinfunction "IO3_108") (pintype "passive"))
    )
    (net (code "77") (name "unconnected-(U$2A-IO4-Pad105)") (class "Default")
      (node (ref "U$2") (pin "105") (pinfunction "IO4_105") (pintype "passive"))
    )
    (net (code "78") (name "unconnected-(U$2A-IO5-Pad106)") (class "Default")
      (node (ref "U$2") (pin "106") (pinfunction "IO5_106") (pintype "passive"))
    )
    (net (code "79") (name "unconnected-(U$2A-UART0_RX-Pad120)") (class "Default")
      (node (ref "U$2") (pin "120") (pinfunction "UART0_RX_120") (pintype "passive"))
    )
    (net (code "80") (name "unconnected-(U$2A-UART0_TX-Pad119)") (class "Default")
      (node (ref "U$2") (pin "119") (pinfunction "UART0_TX_119") (pintype "passive"))
    )
    (net (code "81") (name "unconnected-(U$2A-UART1_RX-Pad118)") (class "Default")
      (node (ref "U$2") (pin "118") (pinfunction "UART1_RX_118") (pintype "passive"))
    )
    (net (code "82") (name "unconnected-(U$2A-UART1_TX-Pad117)") (class "Default")
      (node (ref "U$2") (pin "117") (pinfunction "UART1_TX_117") (pintype "passive"))
    )
    (net (code "83") (name "unconnected-(U$2A-USB_DN-Pad111)") (class "Default")
      (node (ref "U$2") (pin "111") (pinfunction "USB_DN_111") (pintype "passive"))
    )
    (net (code "84") (name "unconnected-(U$2A-USB_DP-Pad112)") (class "Default")
      (node (ref "U$2") (pin "112") (pinfunction "USB_DP_112") (pintype "passive"))
    )
    (net (code "85") (name "unconnected-(U$2B-GND0-Pad2)") (class "Default")
      (node (ref "U$2") (pin "2") (pinfunction "GND0_2") (pintype "passive"))
    )
    (net (code "86") (name "unconnected-(U$2B-GND1-Pad4)") (class "Default")
      (node (ref "U$2") (pin "4") (pinfunction "GND1_4") (pintype "passive"))
    )
    (net (code "87") (name "unconnected-(U$2B-GND2-Pad6)") (class "Default")
      (node (ref "U$2") (pin "6") (pinfunction "GND2_6") (pintype "passive"))
    )
    (net (code "88") (name "unconnected-(U$2B-GND3-Pad8)") (class "Default")
      (node (ref "U$2") (pin "8") (pinfunction "GND3_8") (pintype "passive"))
    )
    (net (code "89") (name "unconnected-(U$2B-GND4-Pad10)") (class "Default")
      (node (ref "U$2") (pin "10") (pinfunction "GND4_10") (pintype "passive"))
    )
    (net (code "90") (name "unconnected-(U$2B-GND5-Pad12)") (class "Default")
      (node (ref "U$2") (pin "12") (pinfunction "GND5_12") (pintype "passive"))
    )
    (net (code "91") (name "unconnected-(U$2B-GND6-Pad14)") (class "Default")
      (node (ref "U$2") (pin "14") (pinfunction "GND6_14") (pintype "passive"))
    )
    (net (code "92") (name "unconnected-(U$2B-GND7-Pad16)") (class "Default")
      (node (ref "U$2") (pin "16") (pinfunction "GND7_16") (pintype "passive"))
    )
    (net (code "93") (name "unconnected-(U$2B-GND9-Pad20)") (class "Default")
      (node (ref "U$2") (pin "20") (pinfunction "GND9_20") (pintype "passive"))
    )
    (net (code "94") (name "unconnected-(U$2B-VCC0-Pad1)") (class "Default")
      (node (ref "U$2") (pin "1") (pinfunction "VCC0_1") (pintype "passive"))
    )
    (net (code "95") (name "unconnected-(U$2B-VCC1-Pad3)") (class "Default")
      (node (ref "U$2") (pin "3") (pinfunction "VCC1_3") (pintype "passive"))
    )
    (net (code "96") (name "unconnected-(U$2B-VCC2-Pad5)") (class "Default")
      (node (ref "U$2") (pin "5") (pinfunction "VCC2_5") (pintype "passive"))
    )
    (net (code "97") (name "unconnected-(U$2B-VCC3-Pad7)") (class "Default")
      (node (ref "U$2") (pin "7") (pinfunction "VCC3_7") (pintype "passive"))
    )
    (net (code "98") (name "unconnected-(U$2B-VCC4-Pad9)") (class "Default")
      (node (ref "U$2") (pin "9") (pinfunction "VCC4_9") (pintype "passive"))
    )
    (net (code "99") (name "unconnected-(U$2B-VCC5-Pad11)") (class "Default")
      (node (ref "U$2") (pin "11") (pinfunction "VCC5_11") (pintype "passive"))
    )
    (net (code "100") (name "unconnected-(U$2B-VCC6-Pad13)") (class "Default")
      (node (ref "U$2") (pin "13") (pinfunction "VCC6_13") (pintype "passive"))
    )
    (net (code "101") (name "unconnected-(U$2B-VCC7-Pad15)") (class "Default")
      (node (ref "U$2") (pin "15") (pinfunction "VCC7_15") (pintype "passive"))
    )
    (net (code "102") (name "unconnected-(U$2B-VCC9-Pad19)") (class "Default")
      (node (ref "U$2") (pin "19") (pinfunction "VCC9_19") (pintype "passive"))
    )
  )
)
